# power.net
KiCad netlist of a schematic drawn in Altium Designer
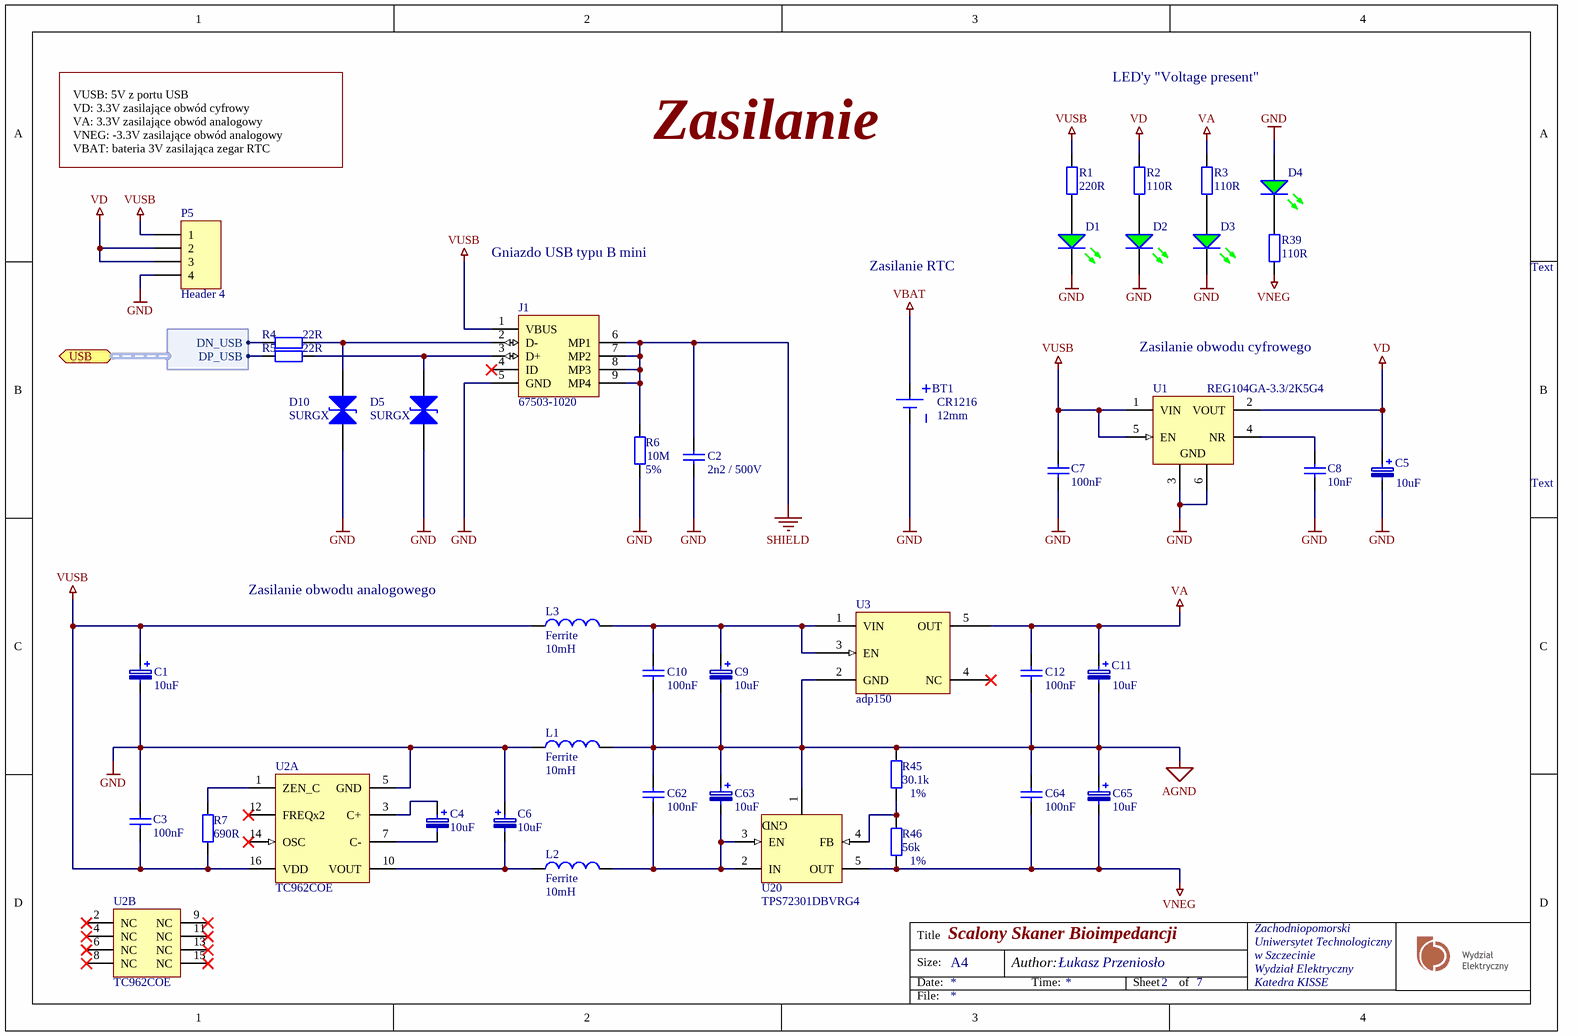
[diagram p0: power.SchDoc]

(export (version "E")
  (design (tool "Eeschema 10.0.6"))
  (components
    (comp (ref "BT1")
      (value "CR1216")
      (footprint "12mm-battery-holder:12MM-BATTERY-HOLDER")
      (description "Lithium Battery Holder for CR2032 3V Cell")
      (fields
        (field (name "MANUFACTURER") "TE Connectivity")
        (field (name "PARTNUMBER") "120591-1")
        (field (name "SIZE") "12mm")
      )
      (libsource (lib "Altium Content Vault") (part "TECO-120591-1-2"))
    )
    (comp (ref "C1")
      (value "10uF")
      (footprint "Mechatronic:SMDA")
      (description "Polarized Capacitor (Surface Mount)")
      (libsource (lib "Mechatronic") (part "10uF 10V-SMDA"))
    )
    (comp (ref "C2")
      (value "2n2 / 500V")
      (footprint "CAPC3216N")
      (description "Capacitor")
      (libsource (lib "Discrete") (part "Capacitor"))
    )
    (comp (ref "C3")
      (value "100nF")
      (footprint "CAPC1608N")
      (description "Capacitor")
      (libsource (lib "Discrete") (part "Capacitor"))
    )
    (comp (ref "C4")
      (value "10uF")
      (footprint "Mechatronic:SMDA")
      (description "Polarized Capacitor (Surface Mount)")
      (libsource (lib "Mechatronic") (part "100uF 6.3V-SMDB"))
    )
    (comp (ref "C5")
      (value "10uF")
      (footprint "Mechatronic:SMDA")
      (description "Polarized Capacitor (Surface Mount)")
      (libsource (lib "Mechatronic") (part "100uF 6.3V-SMDB"))
    )
    (comp (ref "C6")
      (value "10uF")
      (footprint "Mechatronic:SMDA")
      (description "Polarized Capacitor (Surface Mount)")
      (libsource (lib "") (part "100uF 6.3V-SMDB_1"))
    )
    (comp (ref "C7")
      (value "100nF")
      (footprint "CAPC1608N")
      (description "Capacitor")
      (libsource (lib "Discrete") (part "Capacitor"))
    )
    (comp (ref "C8")
      (value "10nF")
      (footprint "CAPC1608N")
      (description "Capacitor")
      (libsource (lib "Discrete") (part "Capacitor"))
    )
    (comp (ref "C9")
      (value "10uF")
      (footprint "Mechatronic:SMDA")
      (description "Polarized Capacitor (Surface Mount)")
      (libsource (lib "Mechatronic") (part "100uF 6.3V-SMDB"))
    )
    (comp (ref "C10")
      (value "100nF")
      (footprint "CAPC1608N")
      (description "Capacitor")
      (libsource (lib "Discrete") (part "Capacitor"))
    )
    (comp (ref "C11")
      (value "10uF")
      (footprint "Mechatronic:SMDA")
      (description "Polarized Capacitor (Surface Mount)")
      (libsource (lib "Mechatronic") (part "100uF 6.3V-SMDB"))
    )
    (comp (ref "C12")
      (value "100nF")
      (footprint "CAPC1608N")
      (description "Capacitor")
      (libsource (lib "Discrete") (part "Capacitor"))
    )
    (comp (ref "C62")
      (value "100nF")
      (footprint "CAPC1608N")
      (description "Capacitor")
      (libsource (lib "Discrete") (part "Capacitor"))
    )
    (comp (ref "C63")
      (value "10uF")
      (footprint "Mechatronic:SMDA")
      (description "Polarized Capacitor (Surface Mount)")
      (libsource (lib "Mechatronic") (part "100uF 6.3V-SMDB"))
    )
    (comp (ref "C64")
      (value "100nF")
      (footprint "CAPC1608N")
      (description "Capacitor")
      (libsource (lib "Discrete") (part "Capacitor"))
    )
    (comp (ref "C65")
      (value "10uF")
      (footprint "Mechatronic:SMDA")
      (description "Polarized Capacitor (Surface Mount)")
      (libsource (lib "Mechatronic") (part "100uF 6.3V-SMDB"))
    )
    (comp (ref "D1")
      (value "LL-S172GC-2A")
      (footprint "Chip Diode - 2 Contacts:CD2012-0805")
      (description "Typical GREEN LED")
      (fields (field (name "MANUFACTURER") "Lucky Light"))
      (libsource (lib "Discrete") (part "Led Green"))
    )
    (comp (ref "D2")
      (value "LL-S172GC-2A")
      (footprint "Chip Diode - 2 Contacts:CD2012-0805")
      (description "Typical GREEN LED")
      (fields (field (name "MANUFACTURER") "Lucky Light"))
      (libsource (lib "Discrete") (part "Led Green"))
    )
    (comp (ref "D3")
      (value "LL-S172GC-2A")
      (footprint "Chip Diode - 2 Contacts:CD2012-0805")
      (description "Typical GREEN LED")
      (fields (field (name "MANUFACTURER") "Lucky Light"))
      (libsource (lib "Discrete") (part "Led Green"))
    )
    (comp (ref "D4")
      (value "LL-S172GC-2A")
      (footprint "Chip Diode - 2 Contacts:CD2012-0805")
      (description "Typical GREEN LED")
      (fields (field (name "MANUFACTURER") "Lucky Light"))
      (libsource (lib "Discrete") (part "Led Green"))
    )
    (comp (ref "D5")
      (value "SURGX")
      (footprint "SURGX-0603")
      (description "ESD Suppressor")
      (libsource (lib "Mechatronic") (part "SURGX"))
    )
    (comp (ref "D10")
      (value "SURGX")
      (footprint "SURGX-0603")
      (description "ESD Suppressor")
      (libsource (lib "Mechatronic") (part "SURGX"))
    )
    (comp (ref "J1")
      (value "67503-1020")
      (footprint "MOLX-67503-1020_V:MOLX-67503-1020_V")
      (description "USB, MINI, SMD, RA KME04-USBMU03A01")
      (fields (field (name "MANUFACTURER") "Molex"))
      (libsource (lib "Altium Content Vault") (part "CMP-0411-00002-1"))
    )
    (comp (ref "L1")
      (value "Ferrite")
      (footprint "FERRITE_1206")
      (description "Inductor")
      (fields (field (name "ALTIUM_VALUE") "10mH") (field (name "PUBLISHER") "Altium Limited"))
      (libsource (lib "Miscellaneous Devices") (part "Inductor"))
    )
    (comp (ref "L2")
      (value "Ferrite")
      (footprint "FERRITE_1206")
      (description "Inductor")
      (fields (field (name "ALTIUM_VALUE") "10mH") (field (name "PUBLISHER") "Altium Limited"))
      (libsource (lib "Miscellaneous Devices") (part "Inductor"))
    )
    (comp (ref "L3")
      (value "Ferrite")
      (footprint "FERRITE_1206")
      (description "Inductor")
      (fields (field (name "ALTIUM_VALUE") "10mH") (field (name "PUBLISHER") "Altium Limited"))
      (libsource (lib "Miscellaneous Devices") (part "Inductor"))
    )
    (comp (ref "P5")
      (value "Header 4")
      (footprint "HDR1X4")
      (description "Header, 4-Pin")
      (fields (field (name "PUBLISHER") "Altium Limited"))
      (libsource (lib "Miscellaneous Connectors") (part "Header 4"))
    )
    (comp (ref "R1")
      (value "220R")
      (footprint "Chip_Resistor_N:RESC1608N")
      (description "Resistor")
      (fields (field (name "TOLERANCE") "5%") (field (name "POWER") "0W"))
      (libsource (lib "Discrete") (part "Resistor"))
    )
    (comp (ref "R2")
      (value "110R")
      (footprint "Chip_Resistor_N:RESC1608N")
      (description "Resistor")
      (fields (field (name "TOLERANCE") "5%") (field (name "POWER") "0W"))
      (libsource (lib "Discrete") (part "Resistor"))
    )
    (comp (ref "R3")
      (value "110R")
      (footprint "Chip_Resistor_N:RESC1608N")
      (description "Resistor")
      (fields (field (name "TOLERANCE") "5%") (field (name "POWER") "0W"))
      (libsource (lib "Discrete") (part "Resistor"))
    )
    (comp (ref "R4")
      (value "22R")
      (footprint "Chip_Resistor_N:RESC1608N")
      (description "Resistor")
      (fields (field (name "TOLERANCE") "5%") (field (name "POWER") "0W"))
      (libsource (lib "") (part "Resistor_2"))
    )
    (comp (ref "R5")
      (value "22R")
      (footprint "Chip_Resistor_N:RESC1608N")
      (description "Resistor")
      (fields (field (name "TOLERANCE") "5%") (field (name "POWER") "0W"))
      (libsource (lib "") (part "Resistor_2"))
    )
    (comp (ref "R6")
      (value "10M")
      (footprint "RESC3216N")
      (description "Resistor")
      (fields (field (name "TOLERANCE") "5%") (field (name "POWER") "0W"))
      (libsource (lib "Discrete") (part "Resistor"))
    )
    (comp (ref "R7")
      (value "690R")
      (footprint "Chip_Resistor_N:RESC1608N")
      (description "Resistor")
      (fields (field (name "TOLERANCE") "5%") (field (name "POWER") "0W"))
      (libsource (lib "") (part "Resistor_2"))
    )
    (comp (ref "R39")
      (value "110R")
      (footprint "Chip_Resistor_N:RESC1608N")
      (description "Resistor")
      (fields (field (name "TOLERANCE") "5%") (field (name "POWER") "0W"))
      (libsource (lib "Discrete") (part "Resistor"))
    )
    (comp (ref "R45")
      (value "30.1k")
      (footprint "Chip_Resistor_N:RESC1608N")
      (description "Resistor")
      (fields (field (name "TOLERANCE") "1%") (field (name "POWER") "0W"))
      (libsource (lib "") (part "Resistor_1"))
    )
    (comp (ref "R46")
      (value "56k")
      (footprint "Chip_Resistor_N:RESC1608N")
      (description "Resistor")
      (fields (field (name "TOLERANCE") "1%") (field (name "POWER") "0W"))
      (libsource (lib "") (part "Resistor_1"))
    )
    (comp (ref "U1")
      (value "REG104GA-3.3/2K5G4")
      (footprint "TI-DCQ6_L:TI-DCQ6_L")
      (fields (field (name "MANUFACTURER") "Texas Instruments"))
      (libsource (lib "Altium Content Vault") (part "CMP-0395-00461-1"))
    )
    (comp (ref "U2")
      (value "TC962COE")
      (footprint "SOIC-OE16_N")
      (description "80mA Charge Pump DC-to-DC Converter, 12kHz, 24kHz, 16-Pin SOIC 300mil, Commercial Temperature")
      (libsource (lib "Altium Content Vault") (part "PM-CHP-TC962-IL16"))
    )
    (comp (ref "U3")
      (value "adp150")
      (footprint "SOT95P280X100-5N")
      (libsource (lib "adp150") (part "adp150"))
    )
    (comp (ref "U20")
      (value "TPS72301DBVRG4")
      (footprint "SOT95P280X100-5N")
      (fields (field (name "MANUFACTURER") "Texas Instruments"))
      (libsource (lib "Altium Content Vault") (part "TI-TPS72301-5"))
    )
  )
  (nets
    (net (code "2") (name "/DN_USB") (class "Default")
      (node (ref "R4") (pin "2") (pinfunction "2_2") (pintype "passive"))
    )
    (net (code "3") (name "/DP_USB") (class "Default")
      (node (ref "R5") (pin "2") (pinfunction "2_2") (pintype "passive"))
    )
    (net (code "5") (name "AGND") (class "Default")
      (node (ref "C10") (pin "1") (pinfunction "1_1") (pintype "passive"))
      (node (ref "C11") (pin "2") (pinfunction "2_2") (pintype "passive"))
      (node (ref "C12") (pin "1") (pinfunction "1_1") (pintype "passive"))
      (node (ref "C62") (pin "2") (pinfunction "2_2") (pintype "passive"))
      (node (ref "C63") (pin "1") (pinfunction "1_1") (pintype "passive"))
      (node (ref "C64") (pin "2") (pinfunction "2_2") (pintype "passive"))
      (node (ref "C65") (pin "1") (pinfunction "1_1") (pintype "passive"))
      (node (ref "C9") (pin "2") (pinfunction "2_2") (pintype "passive"))
      (node (ref "L1") (pin "2") (pinfunction "2_2") (pintype "passive"))
      (node (ref "R45") (pin "1") (pinfunction "1_1") (pintype "passive"))
      (node (ref "U20") (pin "1") (pinfunction "GND_1") (pintype "power_in"))
      (node (ref "U3") (pin "2") (pinfunction "GND_2") (pintype "power_in"))
    )
    (net (code "6") (name "GND") (class "Default")
      (node (ref "BT1") (pin "2") (pinfunction "-_2") (pintype "passive"))
      (node (ref "C1") (pin "2") (pinfunction "2_2") (pintype "passive"))
      (node (ref "C2") (pin "1") (pinfunction "1_1") (pintype "passive"))
      (node (ref "C3") (pin "1") (pinfunction "1_1") (pintype "passive"))
      (node (ref "C5") (pin "2") (pinfunction "2_2") (pintype "passive"))
      (node (ref "C6") (pin "1") (pinfunction "1_1") (pintype "passive"))
      (node (ref "C7") (pin "1") (pinfunction "1_1") (pintype "passive"))
      (node (ref "C8") (pin "1") (pinfunction "1_1") (pintype "passive"))
      (node (ref "D1") (pin "2") (pinfunction "K_2") (pintype "passive"))
      (node (ref "D10") (pin "1") (pinfunction "1_1") (pintype "passive"))
      (node (ref "D2") (pin "2") (pinfunction "K_2") (pintype "passive"))
      (node (ref "D3") (pin "2") (pinfunction "K_2") (pintype "passive"))
      (node (ref "D4") (pin "1") (pinfunction "A_1") (pintype "passive"))
      (node (ref "D5") (pin "1") (pinfunction "1_1") (pintype "passive"))
      (node (ref "J1") (pin "5") (pinfunction "GND_5") (pintype "power_in"))
      (node (ref "L1") (pin "1") (pinfunction "1_1") (pintype "passive"))
      (node (ref "P5") (pin "4") (pinfunction "4_4") (pintype "passive"))
      (node (ref "R6") (pin "1") (pinfunction "1_1") (pintype "passive"))
      (node (ref "U1") (pin "3") (pinfunction "GND_3") (pintype "power_in"))
      (node (ref "U1") (pin "6") (pinfunction "GND_6") (pintype "power_in"))
      (node (ref "U2") (pin "5") (pinfunction "GND_5") (pintype "power_in"))
    )
    (net (code "7") (name "Net-(D1-A)") (class "Default")
      (node (ref "D1") (pin "1") (pinfunction "A_1") (pintype "passive"))
      (node (ref "R1") (pin "1") (pinfunction "1_1") (pintype "passive"))
    )
    (net (code "8") (name "Net-(D2-A)") (class "Default")
      (node (ref "D2") (pin "1") (pinfunction "A_1") (pintype "passive"))
      (node (ref "R2") (pin "1") (pinfunction "1_1") (pintype "passive"))
    )
    (net (code "9") (name "Net-(D3-A)") (class "Default")
      (node (ref "D3") (pin "1") (pinfunction "A_1") (pintype "passive"))
      (node (ref "R3") (pin "1") (pinfunction "1_1") (pintype "passive"))
    )
    (net (code "10") (name "Net-(D4-K)") (class "Default")
      (node (ref "D4") (pin "2") (pinfunction "K_2") (pintype "passive"))
      (node (ref "R39") (pin "2") (pinfunction "2_2") (pintype "passive"))
    )
    (net (code "11") (name "Net-(J1-D+)") (class "Default")
      (node (ref "D5") (pin "2") (pinfunction "2_2") (pintype "passive"))
      (node (ref "J1") (pin "3") (pinfunction "D+_3") (pintype "bidirectional"))
      (node (ref "R5") (pin "1") (pinfunction "1_1") (pintype "passive"))
    )
    (net (code "12") (name "Net-(J1-D-)") (class "Default")
      (node (ref "D10") (pin "2") (pinfunction "2_2") (pintype "passive"))
      (node (ref "J1") (pin "2") (pinfunction "D-_2") (pintype "bidirectional"))
      (node (ref "R4") (pin "1") (pinfunction "1_1") (pintype "passive"))
    )
    (net (code "13") (name "Net-(U1-NR)") (class "Default")
      (node (ref "C8") (pin "2") (pinfunction "2_2") (pintype "passive"))
      (node (ref "U1") (pin "4") (pinfunction "NR_4") (pintype "passive"))
    )
    (net (code "14") (name "Net-(U2A-C+)") (class "Default")
      (node (ref "C4") (pin "1") (pinfunction "1_1") (pintype "passive"))
      (node (ref "U2") (pin "3") (pinfunction "C+_3") (pintype "passive"))
    )
    (net (code "15") (name "Net-(U2A-C-)") (class "Default")
      (node (ref "C4") (pin "2") (pinfunction "2_2") (pintype "passive"))
      (node (ref "U2") (pin "7") (pinfunction "C-_7") (pintype "passive"))
    )
    (net (code "16") (name "Net-(U2A-VOUT)") (class "Default")
      (node (ref "C6") (pin "2") (pinfunction "2_2") (pintype "passive"))
      (node (ref "L2") (pin "1") (pinfunction "1_1") (pintype "passive"))
      (node (ref "U2") (pin "10") (pinfunction "VOUT_10") (pintype "power_in"))
    )
    (net (code "17") (name "Net-(U2A-ZEN_C)") (class "Default")
      (node (ref "R7") (pin "1") (pinfunction "1_1") (pintype "passive"))
      (node (ref "U2") (pin "1") (pinfunction "ZEN_C_1") (pintype "passive"))
    )
    (net (code "18") (name "Net-(U3-EN)") (class "Default")
      (node (ref "C10") (pin "2") (pinfunction "2_2") (pintype "passive"))
      (node (ref "C9") (pin "1") (pinfunction "1_1") (pintype "passive"))
      (node (ref "L3") (pin "2") (pinfunction "2_2") (pintype "passive"))
      (node (ref "U3") (pin "1") (pinfunction "VIN_1") (pintype "power_in"))
      (node (ref "U3") (pin "3") (pinfunction "EN_3") (pintype "input"))
    )
    (net (code "19") (name "Net-(U20-EN)") (class "Default")
      (node (ref "C62") (pin "1") (pinfunction "1_1") (pintype "passive"))
      (node (ref "C63") (pin "2") (pinfunction "2_2") (pintype "passive"))
      (node (ref "L2") (pin "2") (pinfunction "2_2") (pintype "passive"))
      (node (ref "U20") (pin "2") (pinfunction "IN_2") (pintype "power_in"))
      (node (ref "U20") (pin "3") (pinfunction "EN_3") (pintype "input"))
    )
    (net (code "20") (name "Net-(U20-FB)") (class "Default")
      (node (ref "R45") (pin "2") (pinfunction "2_2") (pintype "passive"))
      (node (ref "R46") (pin "1") (pinfunction "1_1") (pintype "passive"))
      (node (ref "U20") (pin "4") (pinfunction "FB_4") (pintype "input"))
    )
    (net (code "21") (name "SHIELD") (class "Default")
      (node (ref "C2") (pin "2") (pinfunction "2_2") (pintype "passive"))
      (node (ref "J1") (pin "6") (pinfunction "MP1_6") (pintype "passive"))
      (node (ref "J1") (pin "7") (pinfunction "MP2_7") (pintype "passive"))
      (node (ref "J1") (pin "8") (pinfunction "MP3_8") (pintype "passive"))
      (node (ref "J1") (pin "9") (pinfunction "MP4_9") (pintype "passive"))
      (node (ref "R6") (pin "2") (pinfunction "2_2") (pintype "passive"))
    )
    (net (code "22") (name "VA") (class "Default")
      (node (ref "C11") (pin "1") (pinfunction "1_1") (pintype "passive"))
      (node (ref "C12") (pin "2") (pinfunction "2_2") (pintype "passive"))
      (node (ref "R3") (pin "2") (pinfunction "2_2") (pintype "passive"))
      (node (ref "U3") (pin "5") (pinfunction "OUT_5") (pintype "power_in"))
    )
    (net (code "23") (name "VBAT") (class "Default")
      (node (ref "BT1") (pin "1") (pinfunction "+_1") (pintype "passive"))
    )
    (net (code "24") (name "VD") (class "Default")
      (node (ref "C5") (pin "1") (pinfunction "1_1") (pintype "passive"))
      (node (ref "P5") (pin "2") (pinfunction "2_2") (pintype "passive"))
      (node (ref "P5") (pin "3") (pinfunction "3_3") (pintype "passive"))
      (node (ref "R2") (pin "2") (pinfunction "2_2") (pintype "passive"))
      (node (ref "U1") (pin "2") (pinfunction "VOUT_2") (pintype "power_in"))
    )
    (net (code "25") (name "VNEG") (class "Default")
      (node (ref "C64") (pin "1") (pinfunction "1_1") (pintype "passive"))
      (node (ref "C65") (pin "2") (pinfunction "2_2") (pintype "passive"))
      (node (ref "R39") (pin "1") (pinfunction "1_1") (pintype "passive"))
      (node (ref "R46") (pin "2") (pinfunction "2_2") (pintype "passive"))
      (node (ref "U20") (pin "5") (pinfunction "OUT_5") (pintype "power_in"))
    )
    (net (code "26") (name "VUSB") (class "Default")
      (node (ref "C1") (pin "1") (pinfunction "1_1") (pintype "passive"))
      (node (ref "C3") (pin "2") (pinfunction "2_2") (pintype "passive"))
      (node (ref "C7") (pin "2") (pinfunction "2_2") (pintype "passive"))
      (node (ref "J1") (pin "1") (pinfunction "VBUS_1") (pintype "power_in"))
      (node (ref "L3") (pin "1") (pinfunction "1_1") (pintype "passive"))
      (node (ref "P5") (pin "1") (pinfunction "1_1") (pintype "passive"))
      (node (ref "R1") (pin "2") (pinfunction "2_2") (pintype "passive"))
      (node (ref "R7") (pin "2") (pinfunction "2_2") (pintype "passive"))
      (node (ref "U1") (pin "1") (pinfunction "VIN_1") (pintype "power_in"))
      (node (ref "U1") (pin "5") (pinfunction "EN_5") (pintype "input"))
      (node (ref "U2") (pin "16") (pinfunction "VDD_16") (pintype "power_in"))
    )
    (net (code "27") (name "unconnected-(J1-ID-Pad4)") (class "Default")
      (node (ref "J1") (pin "4") (pinfunction "ID_4") (pintype "passive+no_connect"))
    )
    (net (code "28") (name "unconnected-(U2A-FREQx2-Pad12)") (class "Default")
      (node (ref "U2") (pin "12") (pinfunction "FREQx2_12") (pintype "passive+no_connect"))
    )
    (net (code "29") (name "unconnected-(U2A-OSC-Pad14)") (class "Default")
      (node (ref "U2") (pin "14") (pinfunction "OSC_14") (pintype "input+no_connect"))
    )
    (net (code "30") (name "unconnected-(U2B-NC-Pad2)") (class "Default")
      (node (ref "U2") (pin "2") (pinfunction "NC_2") (pintype "passive+no_connect"))
    )
    (net (code "31") (name "unconnected-(U2B-NC-Pad4)") (class "Default")
      (node (ref "U2") (pin "4") (pinfunction "NC_4") (pintype "passive+no_connect"))
    )
    (net (code "32") (name "unconnected-(U2B-NC-Pad6)") (class "Default")
      (node (ref "U2") (pin "6") (pinfunction "NC_6") (pintype "passive+no_connect"))
    )
    (net (code "33") (name "unconnected-(U2B-NC-Pad8)") (class "Default")
      (node (ref "U2") (pin "8") (pinfunction "NC_8") (pintype "passive+no_connect"))
    )
    (net (code "34") (name "unconnected-(U2B-NC-Pad9)") (class "Default")
      (node (ref "U2") (pin "9") (pinfunction "NC_9") (pintype "passive+no_connect"))
    )
    (net (code "35") (name "unconnected-(U2B-NC-Pad11)") (class "Default")
      (node (ref "U2") (pin "11") (pinfunction "NC_11") (pintype "passive+no_connect"))
    )
    (net (code "36") (name "unconnected-(U2B-NC-Pad13)") (class "Default")
      (node (ref "U2") (pin "13") (pinfunction "NC_13") (pintype "passive+no_connect"))
    )
    (net (code "37") (name "unconnected-(U2B-NC-Pad15)") (class "Default")
      (node (ref "U2") (pin "15") (pinfunction "NC_15") (pintype "passive+no_connect"))
    )
    (net (code "38") (name "unconnected-(U3-NC-Pad4)") (class "Default")
      (node (ref "U3") (pin "4") (pinfunction "NC_4") (pintype "passive+no_connect"))
    )
  )
)
